# Battery.net
KiCad netlist of a schematic drawn in Altium Designer
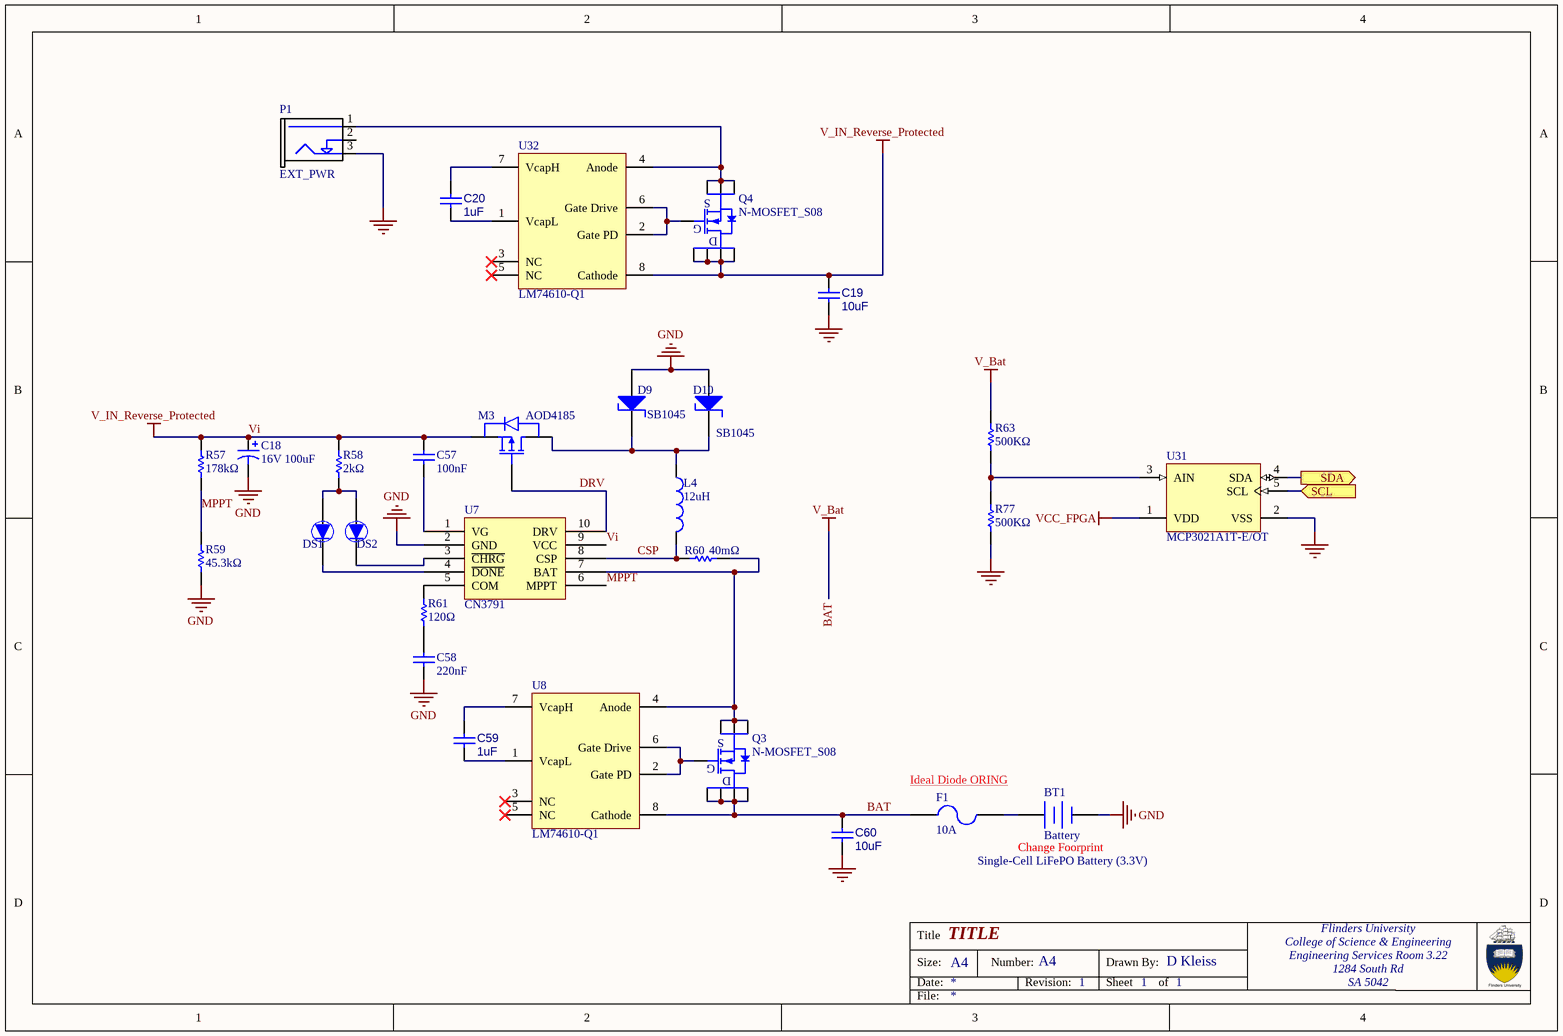
[diagram p0: Battery.SchDoc]

(export (version "E")
  (design (tool "Eeschema 10.0.6"))
  (components
    (comp (ref "BT1")
      (value "Battery")
      (footprint "CONNECTOR PHOENIX 1757242")
      (description "Multicell Battery")
      (fields (field (name "MANUFACTURER") "Phoenix"))
      (libsource (lib "Miscellaneous Devices") (part "Battery"))
    )
    (comp (ref "C18")
      (value "16V 100uF")
      (footprint "KEMT-T491-D_L")
      (description "有極性電容")
      (libsource (lib "澄 library") (part "cap"))
    )
    (comp (ref "C19")
      (value "10uF")
      (footprint "0603_CAP UF HD")
      (description "Capacitor")
      (fields (field (name "MANUFACTURER") "Murata"))
      (libsource (lib "Workshop Library 2010_06_24") (part "Cap"))
    )
    (comp (ref "C20")
      (value "1uF")
      (footprint "0603_CAP UF HD")
      (description "Capacitor")
      (fields (field (name "MANUFACTURER") "Samsung"))
      (libsource (lib "Workshop Library 2010_06_24") (part "Cap"))
    )
    (comp (ref "C57")
      (value "100nF")
      (footprint "0603_CAP UF HD")
      (libsource (lib "澄 library") (part "cap2"))
    )
    (comp (ref "C58")
      (value "220nF")
      (footprint "0603_CAP UF HD")
      (libsource (lib "澄 library") (part "cap2"))
    )
    (comp (ref "C59")
      (value "1uF")
      (footprint "0603_CAP UF HD")
      (description "Capacitor")
      (fields (field (name "MANUFACTURER") "Samsung"))
      (libsource (lib "Workshop Library 2010_06_24") (part "Cap"))
    )
    (comp (ref "C60")
      (value "10uF")
      (footprint "0603_CAP UF HD")
      (description "Capacitor")
      (fields (field (name "MANUFACTURER") "Murata"))
      (libsource (lib "Workshop Library 2010_06_24") (part "Cap"))
    )
    (comp (ref "D9")
      (value "SB1045")
      (footprint "FP-95570-MFG")
      (description "10.0A SCHOTTKY BARRIER RECTIFIER")
      (libsource (lib "澄 library") (part "SB1045"))
    )
    (comp (ref "D10")
      (value "SB1045")
      (footprint "FP-95570-MFG")
      (description "10.0A SCHOTTKY BARRIER RECTIFIER")
      (libsource (lib "澄 library") (part "SB1045"))
    )
    (comp (ref "DS1") (value "LED") (footprint "3.2X1.6X1.1") (libsource (lib "澄 library") (part "LED")))
    (comp (ref "DS2")
      (value "LED")
      (footprint "3.2X1.6X1.1")
      (libsource (lib "Miscellaneous Devices") (part "LED"))
    )
    (comp (ref "F1")
      (value "10A")
      (footprint "FUSE OMF125")
      (description "Fuse")
      (fields (field (name "MANUFACTURER") "Schurter Inc."))
      (libsource (lib "Workshop Library 2010_06_24") (part "Fuse"))
    )
    (comp (ref "L4") (value "12uH") (footprint "WE-PD-L") (libsource (lib "澄 library") (part "inductor_1")))
    (comp (ref "M3")
      (value "AOD4185")
      (footprint "FP-C04-189-MFG")
      (description "P-Channel Enhancement Mode Field Effect Transistor")
      (libsource (lib "澄 library") (part "AOD4185"))
    )
    (comp (ref "P1")
      (value "EXT_PWR")
      (footprint "DCPOWER - P0620")
      (description "2.1mm DC JACK")
      (fields (field (name "MANUFACTURER") "Wurth Electronics Inc."))
      (libsource (lib "Workshop Library 2010_06_24") (part "DCPOWER"))
    )
    (comp (ref "Q3")
      (value "N-MOSFET_S08")
      (footprint "SOIC-8-H_SLDR")
      (description "N-Mosfet SOIC-8")
      (libsource (lib "Workshop Library 2010_06_24") (part "N-MOSFET_S08"))
    )
    (comp (ref "Q4")
      (value "N-MOSFET_S08")
      (footprint "SOIC-8-H_SLDR")
      (description "N-Mosfet SOIC-8")
      (libsource (lib "Workshop Library 2010_06_24") (part "N-MOSFET_S08"))
    )
    (comp (ref "R57")
      (value "178kΩ")
      (footprint "1608[0603]")
      (description "Resistor")
      (fields (field (name "PUBLISHER") "Altium Limited"))
      (libsource (lib "myLib2009") (part "Res"))
    )
    (comp (ref "R58")
      (value "2kΩ")
      (footprint "1608[0603]")
      (description "Resistor")
      (fields (field (name "PUBLISHER") "Altium Limited"))
      (libsource (lib "myLib2009") (part "Res"))
    )
    (comp (ref "R59")
      (value "45.3kΩ")
      (footprint "1608[0603]")
      (description "Resistor")
      (fields (field (name "PUBLISHER") "Altium Limited"))
      (libsource (lib "myLib2009") (part "Res"))
    )
    (comp (ref "R60")
      (value "40mΩ")
      (footprint "0603-RESISTOR HD")
      (description "R sense")
      (libsource (lib "澄 library") (part "Res"))
    )
    (comp (ref "R61")
      (value "120Ω")
      (footprint "1608[0603]")
      (description "Resistor")
      (fields (field (name "PUBLISHER") "Altium Limited"))
      (libsource (lib "myLib2009") (part "Res"))
    )
    (comp (ref "R63")
      (value "500KΩ")
      (footprint "0603-RESISTOR HD")
      (description "R sense")
      (libsource (lib "澄 library") (part "Res"))
    )
    (comp (ref "R77")
      (value "500KΩ")
      (footprint "0603-RESISTOR HD")
      (description "R sense")
      (libsource (lib "澄 library") (part "Res"))
    )
    (comp (ref "U7")
      (value "CN3791")
      (footprint "CN3795:SSOP10")
      (description "4A, Standalone Li-ion Battery Charger IC  With Photovoltaic Cell MPPT Function")
      (libsource (lib "CN3795") (part "CN3791"))
    )
    (comp (ref "U8")
      (value "LM74610-Q1")
      (footprint "TI-DGK8_V")
      (description "Zero IQ Reverse Polarity Protection Smart Diode Controller")
      (libsource (lib "Workshop Library 2010_06_24") (part "LM74610-Q1"))
    )
    (comp (ref "U31")
      (value "MCP3021A1T-E/OT")
      (footprint "SOT-23-OT5_M")
      (libsource (lib "Altium Content Vault") (part "CON-ADC-MCP3021-5"))
    )
    (comp (ref "U32")
      (value "LM74610-Q1")
      (footprint "TI-DGK8_V")
      (description "Zero IQ Reverse Polarity Protection Smart Diode Controller")
      (libsource (lib "Workshop Library 2010_06_24") (part "LM74610-Q1"))
    )
  )
  (nets
    (net (code "1") (name "/BAT") (class "Default")
      (node (ref "C60") (pin "1") (pinfunction "1_1") (pintype "passive"))
      (node (ref "F1") (pin "2") (pinfunction "2_2") (pintype "passive"))
      (node (ref "Q3") (pin "5") (pinfunction "D_5") (pintype "passive"))
      (node (ref "Q3") (pin "6") (pinfunction "D_6") (pintype "passive"))
      (node (ref "Q3") (pin "7") (pinfunction "D_7") (pintype "passive"))
      (node (ref "Q3") (pin "8") (pinfunction "D_8") (pintype "passive"))
      (node (ref "U8") (pin "8") (pinfunction "Cathode_8") (pintype "passive"))
    )
    (net (code "2") (name "/CSP") (class "Default")
      (node (ref "L4") (pin "2") (pinfunction "2_2") (pintype "passive"))
      (node (ref "R60") (pin "2") (pinfunction "2_2") (pintype "passive"))
      (node (ref "U7") (pin "8") (pinfunction "CSP_8") (pintype "passive"))
    )
    (net (code "3") (name "/DRV") (class "Default")
      (node (ref "M3") (pin "1") (pinfunction "G_1") (pintype "passive"))
      (node (ref "U7") (pin "10") (pinfunction "DRV_10") (pintype "passive"))
    )
    (net (code "4") (name "/MPPT") (class "Default")
      (node (ref "R57") (pin "1") (pinfunction "1_1") (pintype "passive"))
      (node (ref "R59") (pin "2") (pinfunction "2_2") (pintype "passive"))
      (node (ref "U7") (pin "6") (pinfunction "MPPT_6") (pintype "passive"))
    )
    (net (code "5") (name "/SCL") (class "Default")
      (node (ref "U31") (pin "5") (pinfunction "SCL_5") (pintype "input"))
    )
    (net (code "6") (name "/SDA") (class "Default")
      (node (ref "U31") (pin "4") (pinfunction "SDA_4") (pintype "bidirectional"))
    )
    (net (code "7") (name "GND") (class "Default")
      (node (ref "BT1") (pin "2") (pinfunction "-_2") (pintype "passive"))
      (node (ref "C18") (pin "2") (pinfunction "2_2") (pintype "passive"))
      (node (ref "C19") (pin "2") (pinfunction "2_2") (pintype "passive"))
      (node (ref "C58") (pin "1") (pinfunction "1_1") (pintype "passive"))
      (node (ref "C60") (pin "2") (pinfunction "2_2") (pintype "passive"))
      (node (ref "D10") (pin "1") (pinfunction "A_1") (pintype "passive"))
      (node (ref "D9") (pin "1") (pinfunction "A_1") (pintype "passive"))
      (node (ref "P1") (pin "3") (pinfunction "3_3") (pintype "passive"))
      (node (ref "R59") (pin "1") (pinfunction "1_1") (pintype "passive"))
      (node (ref "R77") (pin "2") (pinfunction "2_2") (pintype "passive"))
      (node (ref "U31") (pin "2") (pinfunction "VSS_2") (pintype "power_in"))
      (node (ref "U7") (pin "2") (pinfunction "GND_2") (pintype "passive"))
    )
    (net (code "8") (name "Net-(BT1-+)") (class "Default")
      (node (ref "BT1") (pin "1") (pinfunction "+_1") (pintype "passive"))
      (node (ref "F1") (pin "1") (pinfunction "1_1") (pintype "passive"))
    )
    (net (code "9") (name "Net-(C58-Pad2)") (class "Default")
      (node (ref "C58") (pin "2") (pinfunction "2_2") (pintype "passive"))
      (node (ref "R61") (pin "1") (pinfunction "1_1") (pintype "passive"))
    )
    (net (code "10") (name "Net-(D10-K)") (class "Default")
      (node (ref "D10") (pin "2") (pinfunction "K_2") (pintype "passive"))
      (node (ref "D9") (pin "2") (pinfunction "K_2") (pintype "passive"))
      (node (ref "L4") (pin "1") (pinfunction "1_1") (pintype "passive"))
      (node (ref "M3") (pin "2") (pinfunction "D_2") (pintype "passive"))
    )
    (net (code "11") (name "Net-(DS1-A)") (class "Default")
      (node (ref "DS1") (pin "1") (pinfunction "A_1") (pintype "passive"))
      (node (ref "DS2") (pin "1") (pinfunction "A_1") (pintype "passive"))
      (node (ref "R58") (pin "1") (pinfunction "1_1") (pintype "passive"))
    )
    (net (code "12") (name "Net-(DS1-K)") (class "Default")
      (node (ref "DS1") (pin "2") (pinfunction "K_2") (pintype "passive"))
      (node (ref "U7") (pin "4") (pinfunction "~{DONE}_4") (pintype "passive"))
    )
    (net (code "13") (name "Net-(DS2-K)") (class "Default")
      (node (ref "DS2") (pin "2") (pinfunction "K_2") (pintype "passive"))
      (node (ref "U7") (pin "3") (pinfunction "~{CHRG}_3") (pintype "passive"))
    )
    (net (code "14") (name "Net-(Q3-G)") (class "Default")
      (node (ref "Q3") (pin "4") (pinfunction "G_4") (pintype "passive"))
      (node (ref "U8") (pin "2") (pinfunction "Gate_PD_2") (pintype "passive"))
      (node (ref "U8") (pin "6") (pinfunction "Gate_Drive_6") (pintype "passive"))
    )
    (net (code "15") (name "Net-(Q4-G)") (class "Default")
      (node (ref "Q4") (pin "4") (pinfunction "G_4") (pintype "passive"))
      (node (ref "U32") (pin "2") (pinfunction "Gate_PD_2") (pintype "passive"))
      (node (ref "U32") (pin "6") (pinfunction "Gate_Drive_6") (pintype "passive"))
    )
    (net (code "16") (name "Net-(U7-BAT)") (class "Default")
      (node (ref "Q3") (pin "1") (pinfunction "S_1") (pintype "passive"))
      (node (ref "Q3") (pin "2") (pinfunction "S_2") (pintype "passive"))
      (node (ref "Q3") (pin "3") (pinfunction "S_3") (pintype "passive"))
      (node (ref "R60") (pin "1") (pinfunction "1_1") (pintype "passive"))
      (node (ref "U7") (pin "7") (pinfunction "BAT_7") (pintype "passive"))
      (node (ref "U8") (pin "4") (pinfunction "Anode_4") (pintype "passive"))
    )
    (net (code "17") (name "Net-(U7-COM)") (class "Default")
      (node (ref "R61") (pin "2") (pinfunction "2_2") (pintype "passive"))
      (node (ref "U7") (pin "5") (pinfunction "COM_5") (pintype "passive"))
    )
    (net (code "18") (name "Net-(U7-VG)") (class "Default")
      (node (ref "C57") (pin "1") (pinfunction "1_1") (pintype "passive"))
      (node (ref "U7") (pin "1") (pinfunction "VG_1") (pintype "passive"))
    )
    (net (code "19") (name "Net-(U8-VcapH)") (class "Default")
      (node (ref "C59") (pin "1") (pinfunction "1_1") (pintype "passive"))
      (node (ref "U8") (pin "7") (pinfunction "VcapH_7") (pintype "passive"))
    )
    (net (code "20") (name "Net-(U8-VcapL)") (class "Default")
      (node (ref "C59") (pin "2") (pinfunction "2_2") (pintype "passive"))
      (node (ref "U8") (pin "1") (pinfunction "VcapL_1") (pintype "passive"))
    )
    (net (code "21") (name "Net-(U31-AIN)") (class "Default")
      (node (ref "R63") (pin "2") (pinfunction "2_2") (pintype "passive"))
      (node (ref "R77") (pin "1") (pinfunction "1_1") (pintype "passive"))
      (node (ref "U31") (pin "3") (pinfunction "AIN_3") (pintype "input"))
    )
    (net (code "22") (name "Net-(U32-Anode)") (class "Default")
      (node (ref "P1") (pin "1") (pinfunction "1_1") (pintype "passive"))
      (node (ref "Q4") (pin "1") (pinfunction "S_1") (pintype "passive"))
      (node (ref "Q4") (pin "2") (pinfunction "S_2") (pintype "passive"))
      (node (ref "Q4") (pin "3") (pinfunction "S_3") (pintype "passive"))
      (node (ref "U32") (pin "4") (pinfunction "Anode_4") (pintype "passive"))
    )
    (net (code "23") (name "Net-(U32-VcapH)") (class "Default")
      (node (ref "C20") (pin "1") (pinfunction "1_1") (pintype "passive"))
      (node (ref "U32") (pin "7") (pinfunction "VcapH_7") (pintype "passive"))
    )
    (net (code "24") (name "Net-(U32-VcapL)") (class "Default")
      (node (ref "C20") (pin "2") (pinfunction "2_2") (pintype "passive"))
      (node (ref "U32") (pin "1") (pinfunction "VcapL_1") (pintype "passive"))
    )
    (net (code "25") (name "VCC_FPGA") (class "Default")
      (node (ref "U31") (pin "1") (pinfunction "VDD_1") (pintype "power_in"))
    )
    (net (code "26") (name "V_Bat") (class "Default")
      (node (ref "R63") (pin "1") (pinfunction "1_1") (pintype "passive"))
    )
    (net (code "27") (name "V_IN_Reverse_Protected") (class "Default")
      (node (ref "C18") (pin "1") (pinfunction "1_1") (pintype "passive"))
      (node (ref "C19") (pin "1") (pinfunction "1_1") (pintype "passive"))
      (node (ref "C57") (pin "2") (pinfunction "2_2") (pintype "passive"))
      (node (ref "M3") (pin "3") (pinfunction "S_3") (pintype "passive"))
      (node (ref "Q4") (pin "5") (pinfunction "D_5") (pintype "passive"))
      (node (ref "Q4") (pin "6") (pinfunction "D_6") (pintype "passive"))
      (node (ref "Q4") (pin "7") (pinfunction "D_7") (pintype "passive"))
      (node (ref "Q4") (pin "8") (pinfunction "D_8") (pintype "passive"))
      (node (ref "R57") (pin "2") (pinfunction "2_2") (pintype "passive"))
      (node (ref "R58") (pin "2") (pinfunction "2_2") (pintype "passive"))
      (node (ref "U32") (pin "8") (pinfunction "Cathode_8") (pintype "passive"))
      (node (ref "U7") (pin "9") (pinfunction "VCC_9") (pintype "passive"))
    )
    (net (code "28") (name "unconnected-(P1-Pad2)") (class "Default")
      (node (ref "P1") (pin "2") (pinfunction "2_2") (pintype "passive"))
    )
    (net (code "29") (name "unconnected-(U8-NC-Pad3)") (class "Default")
      (node (ref "U8") (pin "3") (pinfunction "NC_3") (pintype "passive+no_connect"))
    )
    (net (code "30") (name "unconnected-(U8-NC-Pad5)") (class "Default")
      (node (ref "U8") (pin "5") (pinfunction "NC_5") (pintype "passive+no_connect"))
    )
    (net (code "31") (name "unconnected-(U32-NC-Pad3)") (class "Default")
      (node (ref "U32") (pin "3") (pinfunction "NC_3") (pintype "passive+no_connect"))
    )
    (net (code "32") (name "unconnected-(U32-NC-Pad5)") (class "Default")
      (node (ref "U32") (pin "5") (pinfunction "NC_5") (pintype "passive+no_connect"))
    )
  )
)
